# Sonar_Power_Schematic_LT1117.net
KiCad netlist of a schematic drawn in EAGLE
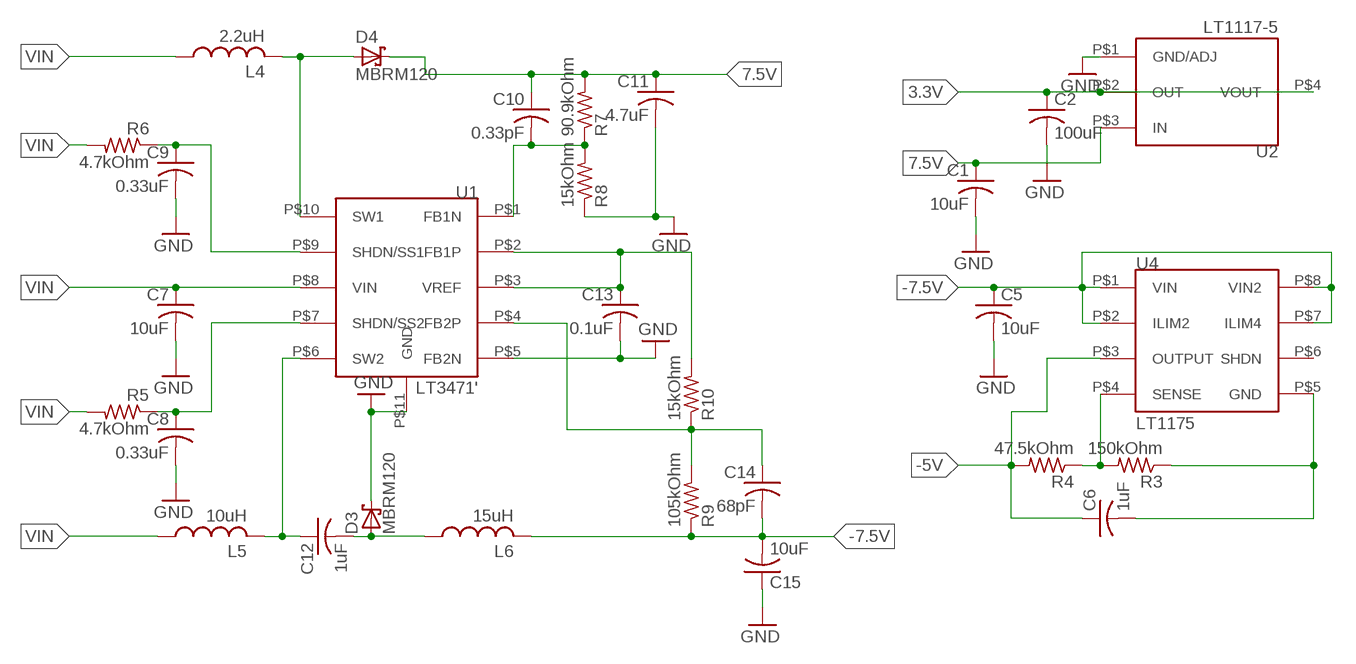
[diagram p0: schematic, sheet 1]

(export (version "E")
  (design (tool "Eeschema 10.0.6"))
  (components
    (comp (ref "C1")
      (value "10uF")
      (footprint "eagle-import:C0603")
      (libsource (lib "eagle-import") (part "C-USC0603"))
    )
    (comp (ref "C2")
      (value "100uF")
      (footprint "eagle-import:C1210")
      (libsource (lib "eagle-import") (part "C-USC1210"))
    )
    (comp (ref "C5")
      (value "10uF")
      (footprint "eagle-import:C0603")
      (libsource (lib "eagle-import") (part "C-USC0603"))
    )
    (comp (ref "C6")
      (value "1uF")
      (footprint "eagle-import:C0603")
      (libsource (lib "eagle-import") (part "C-USC0603"))
    )
    (comp (ref "C7")
      (value "10uF")
      (footprint "eagle-import:C0603")
      (libsource (lib "eagle-import") (part "C-USC0603"))
    )
    (comp (ref "C8")
      (value "0.33uF")
      (footprint "eagle-import:C0603")
      (libsource (lib "eagle-import") (part "C-USC0603"))
    )
    (comp (ref "C9")
      (value "0.33uF")
      (footprint "eagle-import:C0603")
      (libsource (lib "eagle-import") (part "C-USC0603"))
    )
    (comp (ref "C10")
      (value "0.33pF")
      (footprint "eagle-import:C0603")
      (libsource (lib "eagle-import") (part "C-USC0603"))
    )
    (comp (ref "C11")
      (value "4.7uF")
      (footprint "eagle-import:C0603")
      (libsource (lib "eagle-import") (part "C-USC0603"))
    )
    (comp (ref "C12")
      (value "1uF")
      (footprint "eagle-import:C0603")
      (libsource (lib "eagle-import") (part "C-USC0603"))
    )
    (comp (ref "C13")
      (value "0.1uF")
      (footprint "eagle-import:C0603")
      (libsource (lib "eagle-import") (part "C-USC0603"))
    )
    (comp (ref "C14")
      (value "68pF")
      (footprint "eagle-import:C0603")
      (libsource (lib "eagle-import") (part "C-USC0603"))
    )
    (comp (ref "C15")
      (value "10uF")
      (footprint "eagle-import:C0603")
      (libsource (lib "eagle-import") (part "C-USC0603"))
    )
    (comp (ref "D3")
      (value "MBRM120")
      (footprint "eagle-import:DO-216AA")
      (libsource (lib "eagle-import") (part "MBRM120"))
    )
    (comp (ref "D4")
      (value "MBRM120")
      (footprint "eagle-import:DO-216AA")
      (libsource (lib "eagle-import") (part "MBRM120"))
    )
    (comp (ref "L4")
      (value "2.2uH")
      (footprint "eagle-import:NS4.9X4.9")
      (libsource (lib "eagle-import") (part "LQH5BPN2R2N38L"))
    )
    (comp (ref "L5")
      (value "10uH")
      (footprint "eagle-import:NS5X5")
      (libsource (lib "eagle-import") (part "VLS5045EX-100M2"))
    )
    (comp (ref "L6")
      (value "15uH")
      (footprint "eagle-import:NS5X5")
      (libsource (lib "eagle-import") (part "VLS5045EX-150M-CA1"))
    )
    (comp (ref "R3")
      (value "150kOhm")
      (footprint "eagle-import:R0603")
      (libsource (lib "eagle-import") (part "R-US_R0603"))
    )
    (comp (ref "R4")
      (value "47.5kOhm")
      (footprint "eagle-import:R0603")
      (libsource (lib "eagle-import") (part "R-US_R0603"))
    )
    (comp (ref "R5")
      (value "4.7kOhm")
      (footprint "eagle-import:R0603")
      (libsource (lib "eagle-import") (part "R-US_R0603"))
    )
    (comp (ref "R6")
      (value "4.7kOhm")
      (footprint "eagle-import:R0603")
      (libsource (lib "eagle-import") (part "R-US_R0603"))
    )
    (comp (ref "R7")
      (value "90.9kOhm")
      (footprint "eagle-import:R0603")
      (libsource (lib "eagle-import") (part "R-US_R0603"))
    )
    (comp (ref "R8")
      (value "15kOhm")
      (footprint "eagle-import:R0603")
      (libsource (lib "eagle-import") (part "R-US_R0603"))
    )
    (comp (ref "R9")
      (value "105kOhm")
      (footprint "eagle-import:R0603")
      (libsource (lib "eagle-import") (part "R-US_R0603"))
    )
    (comp (ref "R10")
      (value "15kOhm")
      (footprint "eagle-import:R0603")
      (libsource (lib "eagle-import") (part "R-US_R0603"))
    )
    (comp (ref "U1")
      (value "LT3471'")
      (footprint "eagle-import:10-WFDFN")
      (libsource (lib "eagle-import") (part "LT3471'"))
    )
    (comp (ref "U2")
      (value "LT1117-5")
      (footprint "eagle-import:SOT233-3")
      (libsource (lib "eagle-import") (part "LT1117-5"))
    )
    (comp (ref "U4")
      (value "LT1175")
      (footprint "eagle-import:8-SOIC")
      (libsource (lib "eagle-import") (part "LT1175"))
    )
  )
  (nets
    (net (code "1") (name "-5V") (class "Default")
      (node (ref "C6") (pin "1") (pinfunction "1_1") (pintype "passive"))
      (node (ref "R4") (pin "2") (pinfunction "2_2") (pintype "passive"))
      (node (ref "U4") (pin "P$3") (pinfunction "OUTPUT_P$3") (pintype "bidirectional"))
    )
    (net (code "2") (name "-7.5V") (class "Default")
      (node (ref "C14") (pin "2") (pinfunction "2_2") (pintype "passive"))
      (node (ref "C15") (pin "2") (pinfunction "2_2") (pintype "passive"))
      (node (ref "C5") (pin "1") (pinfunction "1_1") (pintype "passive"))
      (node (ref "L6") (pin "P$2") (pinfunction "2_P$2") (pintype "passive"))
      (node (ref "R9") (pin "1") (pinfunction "1_1") (pintype "passive"))
      (node (ref "U4") (pin "P$1") (pinfunction "VIN_P$1") (pintype "power_in"))
      (node (ref "U4") (pin "P$2") (pinfunction "ILIM2_P$2") (pintype "bidirectional"))
      (node (ref "U4") (pin "P$7") (pinfunction "ILIM4_P$7") (pintype "bidirectional"))
      (node (ref "U4") (pin "P$8") (pinfunction "VIN2_P$8") (pintype "power_in"))
    )
    (net (code "3") (name "3.3V") (class "Default")
      (node (ref "C2") (pin "1") (pinfunction "1_1") (pintype "passive"))
      (node (ref "U2") (pin "P$2") (pinfunction "OUT_P$2") (pintype "bidirectional"))
      (node (ref "U2") (pin "P$4") (pinfunction "VOUT_P$4") (pintype "bidirectional"))
    )
    (net (code "4") (name "7.5V") (class "Default")
      (node (ref "C1") (pin "1") (pinfunction "1_1") (pintype "passive"))
      (node (ref "C10") (pin "1") (pinfunction "1_1") (pintype "passive"))
      (node (ref "C11") (pin "1") (pinfunction "1_1") (pintype "passive"))
      (node (ref "D4") (pin "P$1") (pinfunction "C_P$1") (pintype "passive"))
      (node (ref "R7") (pin "2") (pinfunction "2_2") (pintype "passive"))
      (node (ref "U2") (pin "P$3") (pinfunction "IN_P$3") (pintype "bidirectional"))
    )
    (net (code "5") (name "GND") (class "Default")
      (node (ref "C1") (pin "2") (pinfunction "2_2") (pintype "passive"))
      (node (ref "C11") (pin "2") (pinfunction "2_2") (pintype "passive"))
      (node (ref "C13") (pin "2") (pinfunction "2_2") (pintype "passive"))
      (node (ref "C15") (pin "1") (pinfunction "1_1") (pintype "passive"))
      (node (ref "C2") (pin "2") (pinfunction "2_2") (pintype "passive"))
      (node (ref "C5") (pin "2") (pinfunction "2_2") (pintype "passive"))
      (node (ref "C7") (pin "2") (pinfunction "2_2") (pintype "passive"))
      (node (ref "C8") (pin "2") (pinfunction "2_2") (pintype "passive"))
      (node (ref "C9") (pin "2") (pinfunction "2_2") (pintype "passive"))
      (node (ref "D3") (pin "P$1") (pinfunction "C_P$1") (pintype "passive"))
      (node (ref "R8") (pin "1") (pinfunction "1_1") (pintype "passive"))
      (node (ref "U1") (pin "P$11") (pinfunction "GND_P$11") (pintype "power_in"))
      (node (ref "U1") (pin "P$5") (pinfunction "FB2N_P$5") (pintype "bidirectional"))
      (node (ref "U2") (pin "P$1") (pinfunction "GND/ADJ_P$1") (pintype "bidirectional"))
    )
    (net (code "6") (name "Net-(D3-A)") (class "Default")
      (node (ref "C12") (pin "2") (pinfunction "2_2") (pintype "passive"))
      (node (ref "D3") (pin "P$2") (pinfunction "A_P$2") (pintype "passive"))
      (node (ref "L6") (pin "P$1") (pinfunction "1_P$1") (pintype "passive"))
    )
    (net (code "7") (name "Net-(D4-A)") (class "Default")
      (node (ref "D4") (pin "P$2") (pinfunction "A_P$2") (pintype "passive"))
      (node (ref "L4") (pin "P$2") (pinfunction "2_P$2") (pintype "passive"))
      (node (ref "U1") (pin "P$10") (pinfunction "SW1_P$10") (pintype "bidirectional"))
    )
    (net (code "8") (name "Net-(L5-2)") (class "Default")
      (node (ref "C12") (pin "1") (pinfunction "1_1") (pintype "passive"))
      (node (ref "L5") (pin "P$2") (pinfunction "2_P$2") (pintype "passive"))
      (node (ref "U1") (pin "P$6") (pinfunction "SW2_P$6") (pintype "bidirectional"))
    )
    (net (code "9") (name "Net-(U1-FB1N)") (class "Default")
      (node (ref "C10") (pin "2") (pinfunction "2_2") (pintype "passive"))
      (node (ref "R7") (pin "1") (pinfunction "1_1") (pintype "passive"))
      (node (ref "R8") (pin "2") (pinfunction "2_2") (pintype "passive"))
      (node (ref "U1") (pin "P$1") (pinfunction "FB1N_P$1") (pintype "bidirectional"))
    )
    (net (code "10") (name "Net-(U1-FB1P)") (class "Default")
      (node (ref "C13") (pin "1") (pinfunction "1_1") (pintype "passive"))
      (node (ref "R10") (pin "2") (pinfunction "2_2") (pintype "passive"))
      (node (ref "U1") (pin "P$2") (pinfunction "FB1P_P$2") (pintype "bidirectional"))
      (node (ref "U1") (pin "P$3") (pinfunction "VREF_P$3") (pintype "power_in"))
    )
    (net (code "11") (name "Net-(U1-FB2P)") (class "Default")
      (node (ref "C14") (pin "1") (pinfunction "1_1") (pintype "passive"))
      (node (ref "R10") (pin "1") (pinfunction "1_1") (pintype "passive"))
      (node (ref "R9") (pin "2") (pinfunction "2_2") (pintype "passive"))
      (node (ref "U1") (pin "P$4") (pinfunction "FB2P_P$4") (pintype "bidirectional"))
    )
    (net (code "12") (name "Net-(U1-SHDN{slash}SS1)") (class "Default")
      (node (ref "C9") (pin "1") (pinfunction "1_1") (pintype "passive"))
      (node (ref "R6") (pin "1") (pinfunction "1_1") (pintype "passive"))
      (node (ref "U1") (pin "P$9") (pinfunction "SHDN/SS1_P$9") (pintype "bidirectional"))
    )
    (net (code "13") (name "Net-(U1-SHDN{slash}SS2)") (class "Default")
      (node (ref "C8") (pin "1") (pinfunction "1_1") (pintype "passive"))
      (node (ref "R5") (pin "1") (pinfunction "1_1") (pintype "passive"))
      (node (ref "U1") (pin "P$7") (pinfunction "SHDN/SS2_P$7") (pintype "bidirectional"))
    )
    (net (code "14") (name "Net-(U4-GND)") (class "Default")
      (node (ref "C6") (pin "2") (pinfunction "2_2") (pintype "passive"))
      (node (ref "R3") (pin "1") (pinfunction "1_1") (pintype "passive"))
      (node (ref "U4") (pin "P$5") (pinfunction "GND_P$5") (pintype "power_in"))
    )
    (net (code "15") (name "Net-(U4-SENSE)") (class "Default")
      (node (ref "R3") (pin "2") (pinfunction "2_2") (pintype "passive"))
      (node (ref "R4") (pin "1") (pinfunction "1_1") (pintype "passive"))
      (node (ref "U4") (pin "P$4") (pinfunction "SENSE_P$4") (pintype "bidirectional"))
    )
    (net (code "16") (name "VIN") (class "Default")
      (node (ref "C7") (pin "1") (pinfunction "1_1") (pintype "passive"))
      (node (ref "L4") (pin "P$1") (pinfunction "1_P$1") (pintype "passive"))
      (node (ref "L5") (pin "P$1") (pinfunction "1_P$1") (pintype "passive"))
      (node (ref "R5") (pin "2") (pinfunction "2_2") (pintype "passive"))
      (node (ref "R6") (pin "2") (pinfunction "2_2") (pintype "passive"))
      (node (ref "U1") (pin "P$8") (pinfunction "VIN_P$8") (pintype "power_in"))
    )
    (net (code "17") (name "unconnected-(U4-SHDN-PadP$6)") (class "Default")
      (node (ref "U4") (pin "P$6") (pinfunction "SHDN_P$6") (pintype "bidirectional"))
    )
  )
)
